# 12V_PowerSupply_V02.net
KiCad netlist of a schematic drawn in EAGLE
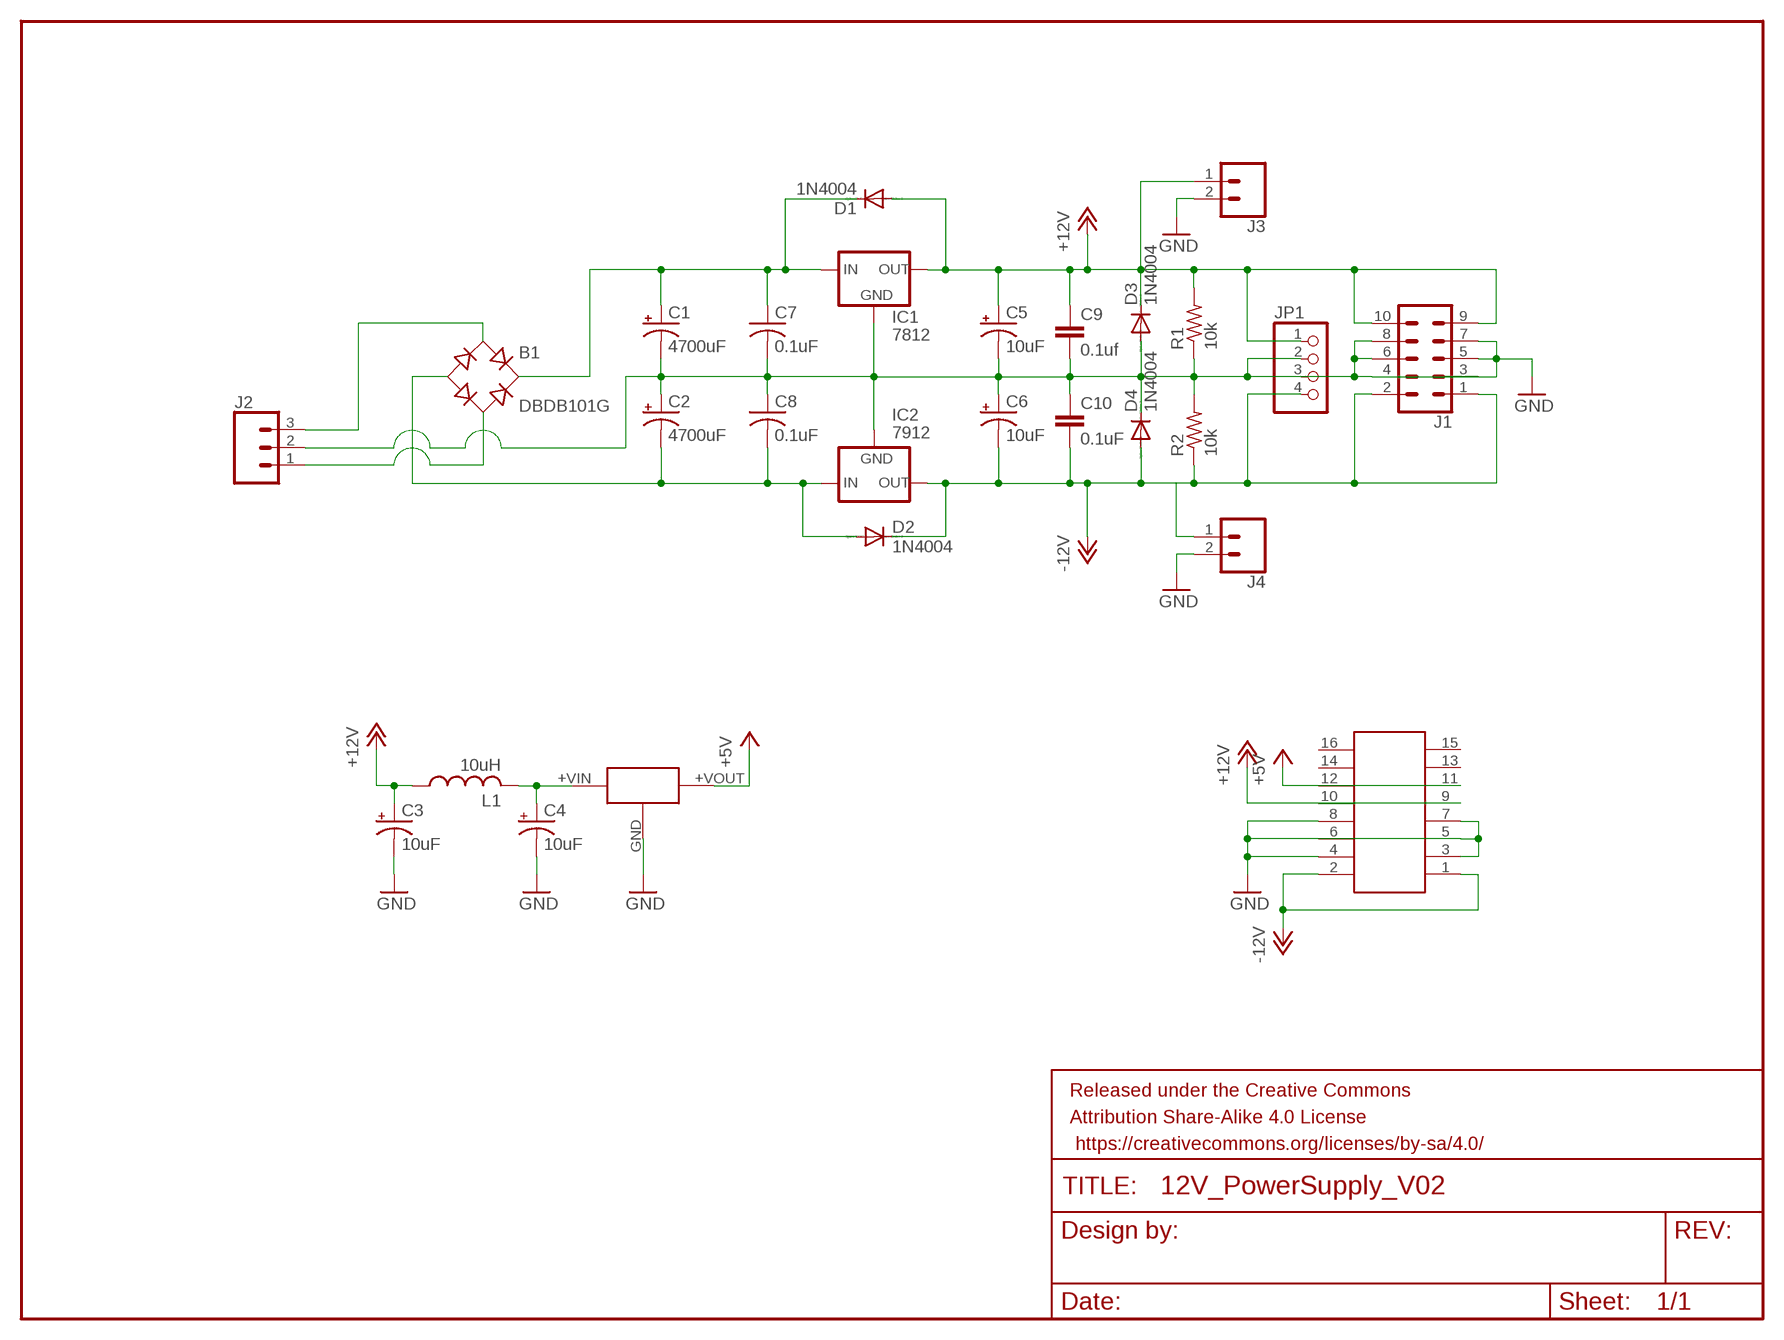
[diagram p0: schematic, sheet 1]

(export (version "E")
  (design (tool "Eeschema 10.0.6"))
  (components
    (comp (ref "B1")
      (value "DBDB101G")
      (footprint "eagle-import:DB")
      (libsource (lib "eagle-import") (part "DB?GDB101"))
    )
    (comp (ref "C1")
      (value "4700uF")
      (footprint "eagle-import:E7,5-18")
      (libsource (lib "eagle-import") (part "CPOL-USE7.5-18"))
    )
    (comp (ref "C2")
      (value "4700uF")
      (footprint "eagle-import:E7,5-18")
      (libsource (lib "eagle-import") (part "CPOL-USE7.5-18"))
    )
    (comp (ref "C3")
      (value "10uF")
      (footprint "eagle-import:E2,5-7")
      (libsource (lib "eagle-import") (part "CPOL-USE2.5-7"))
    )
    (comp (ref "C4")
      (value "10uF")
      (footprint "eagle-import:E2,5-7")
      (libsource (lib "eagle-import") (part "CPOL-USE2.5-7"))
    )
    (comp (ref "C5")
      (value "10uF")
      (footprint "eagle-import:E2,5-7")
      (libsource (lib "eagle-import") (part "CPOL-USE2.5-7"))
    )
    (comp (ref "C6")
      (value "10uF")
      (footprint "eagle-import:E2,5-7")
      (libsource (lib "eagle-import") (part "CPOL-USE2.5-7"))
    )
    (comp (ref "C7")
      (value "0.1uF")
      (footprint "eagle-import:C150-054X183")
      (libsource (lib "eagle-import") (part "C-US150-054X183"))
    )
    (comp (ref "C8")
      (value "0.1uF")
      (footprint "eagle-import:C150-054X183")
      (libsource (lib "eagle-import") (part "C-US150-054X183"))
    )
    (comp (ref "C9")
      (value "0.1uf")
      (footprint "eagle-import:C050-025X075")
      (libsource (lib "eagle-import") (part "C-EU050-025X075"))
    )
    (comp (ref "C10")
      (value "0.1uF")
      (footprint "eagle-import:C050-025X075")
      (libsource (lib "eagle-import") (part "C-EU050-025X075"))
    )
    (comp (ref "D1")
      (value "1N4004")
      (footprint "eagle-import:DO41-10")
      (libsource (lib "eagle-import") (part "1N4004"))
    )
    (comp (ref "D2")
      (value "1N4004")
      (footprint "eagle-import:DO41-10")
      (libsource (lib "eagle-import") (part "1N4004"))
    )
    (comp (ref "D3")
      (value "1N4004")
      (footprint "eagle-import:DO41-10")
      (libsource (lib "eagle-import") (part "1N4004"))
    )
    (comp (ref "D4")
      (value "1N4004")
      (footprint "eagle-import:DO41-10")
      (libsource (lib "eagle-import") (part "1N4004"))
    )
    (comp (ref "FRAME1")
      (value "FRAME-LETTER")
      (footprint "eagle-import:CREATIVE_COMMONS")
      (libsource (lib "eagle-import") (part "FRAME-LETTER"))
    )
    (comp (ref "IC1")
      (value "7812")
      (footprint "eagle-import:78XXS")
      (libsource (lib "eagle-import") (part "78XXS"))
    )
    (comp (ref "IC2")
      (value "7912")
      (footprint "eagle-import:79XXS")
      (libsource (lib "eagle-import") (part "79XXS"))
    )
    (comp (ref "J1")
      (value "CONN_05X2SHD")
      (footprint "eagle-import:2X5-SHROUDED")
      (libsource (lib "eagle-import") (part "CONN_05X2SHD"))
    )
    (comp (ref "J2")
      (value "CONN_03-SCREW-5MM")
      (footprint "eagle-import:SCREWTERMINAL-5MM-3")
      (libsource (lib "eagle-import") (part "CONN_03-SCREW-5MM"))
    )
    (comp (ref "J3")
      (value "CONN_023.5MM-NO_SILK")
      (footprint "eagle-import:SCREWTERMINAL-3.5MM-2-NS")
      (libsource (lib "eagle-import") (part "CONN_023.5MM-NO_SILK"))
    )
    (comp (ref "J4")
      (value "CONN_023.5MM-NO_SILK")
      (footprint "eagle-import:SCREWTERMINAL-3.5MM-2-NS")
      (libsource (lib "eagle-import") (part "CONN_023.5MM-NO_SILK"))
    )
    (comp (ref "JP1")
      (value "PINHD-1X4")
      (footprint "eagle-import:1X04")
      (libsource (lib "eagle-import") (part "PINHD-1X4"))
    )
    (comp (ref "L1")
      (value "10uH")
      (footprint "eagle-import:6000-XXXX-RC")
      (libsource (lib "eagle-import") (part "L-US6000-XXX-RC"))
    )
    (comp (ref "R1")
      (value "10k")
      (footprint "eagle-import:0204_7")
      (libsource (lib "eagle-import") (part "R-US_0204/7"))
    )
    (comp (ref "R2")
      (value "10k")
      (footprint "eagle-import:0204_7")
      (libsource (lib "eagle-import") (part "R-US_0204/7"))
    )
    (comp (ref "U$1")
      (value "8X2_HEADER_SHROUDED")
      (footprint "eagle-import:8X2_HEADER_SHROUDED")
      (libsource (lib "eagle-import") (part "8X2_HEADER_SHROUDED"))
    )
    (comp (ref "U$2")
      (value "R_78E_5V")
      (footprint "eagle-import:R_78E")
      (libsource (lib "eagle-import") (part "R_78E_5V"))
    )
  )
  (nets
    (net (code "1") (name "+5V") (class "Default")
      (node (ref "U$1") (pin "11") (pinfunction "11_11") (pintype "bidirectional"))
      (node (ref "U$1") (pin "12") (pinfunction "12_12") (pintype "bidirectional"))
      (node (ref "U$2") (pin "+VOUT") (pinfunction "+VOUT_+VOUT") (pintype "bidirectional"))
    )
    (net (code "2") (name "+12V") (class "Default")
      (node (ref "C3") (pin "+") (pinfunction "+_+") (pintype "passive"))
      (node (ref "C5") (pin "+") (pinfunction "+_+") (pintype "passive"))
      (node (ref "C9") (pin "1") (pinfunction "1_1") (pintype "passive"))
      (node (ref "D1") (pin "A") (pinfunction "A_A") (pintype "passive"))
      (node (ref "D3") (pin "C") (pinfunction "C_C") (pintype "passive"))
      (node (ref "IC1") (pin "OUT") (pinfunction "OUT_OUT") (pintype "passive"))
      (node (ref "J1") (pin "10") (pinfunction "10_10") (pintype "passive"))
      (node (ref "J1") (pin "9") (pinfunction "9_9") (pintype "passive"))
      (node (ref "J3") (pin "1") (pinfunction "1_1") (pintype "passive"))
      (node (ref "JP1") (pin "1") (pinfunction "1_1") (pintype "passive"))
      (node (ref "L1") (pin "1") (pinfunction "1_1") (pintype "passive"))
      (node (ref "R1") (pin "2") (pinfunction "2_2") (pintype "passive"))
      (node (ref "U$1") (pin "10") (pinfunction "10_10") (pintype "bidirectional"))
      (node (ref "U$1") (pin "9") (pinfunction "9_9") (pintype "bidirectional"))
    )
    (net (code "3") (name "-12V") (class "Default")
      (node (ref "C10") (pin "2") (pinfunction "2_2") (pintype "passive"))
      (node (ref "C6") (pin "-") (pinfunction "-_-") (pintype "passive"))
      (node (ref "D2") (pin "C") (pinfunction "C_C") (pintype "passive"))
      (node (ref "D4") (pin "A") (pinfunction "A_A") (pintype "passive"))
      (node (ref "IC2") (pin "OUT") (pinfunction "OUT_OUT") (pintype "passive"))
      (node (ref "J1") (pin "1") (pinfunction "1_1") (pintype "passive"))
      (node (ref "J1") (pin "2") (pinfunction "2_2") (pintype "passive"))
      (node (ref "J4") (pin "1") (pinfunction "1_1") (pintype "passive"))
      (node (ref "JP1") (pin "4") (pinfunction "4_4") (pintype "passive"))
      (node (ref "R2") (pin "1") (pinfunction "1_1") (pintype "passive"))
      (node (ref "U$1") (pin "1") (pinfunction "1_1") (pintype "bidirectional"))
      (node (ref "U$1") (pin "2") (pinfunction "2_2") (pintype "bidirectional"))
    )
    (net (code "4") (name "GND") (class "Default")
      (node (ref "C1") (pin "-") (pinfunction "-_-") (pintype "passive"))
      (node (ref "C10") (pin "1") (pinfunction "1_1") (pintype "passive"))
      (node (ref "C2") (pin "+") (pinfunction "+_+") (pintype "passive"))
      (node (ref "C3") (pin "-") (pinfunction "-_-") (pintype "passive"))
      (node (ref "C4") (pin "-") (pinfunction "-_-") (pintype "passive"))
      (node (ref "C5") (pin "-") (pinfunction "-_-") (pintype "passive"))
      (node (ref "C6") (pin "+") (pinfunction "+_+") (pintype "passive"))
      (node (ref "C7") (pin "2") (pinfunction "2_2") (pintype "passive"))
      (node (ref "C8") (pin "1") (pinfunction "1_1") (pintype "passive"))
      (node (ref "C9") (pin "2") (pinfunction "2_2") (pintype "passive"))
      (node (ref "D3") (pin "A") (pinfunction "A_A") (pintype "passive"))
      (node (ref "D4") (pin "C") (pinfunction "C_C") (pintype "passive"))
      (node (ref "IC1") (pin "GND") (pinfunction "GND_GND") (pintype "input"))
      (node (ref "IC2") (pin "GND") (pinfunction "GND_GND") (pintype "input"))
      (node (ref "J1") (pin "3") (pinfunction "3_3") (pintype "passive"))
      (node (ref "J1") (pin "4") (pinfunction "4_4") (pintype "passive"))
      (node (ref "J1") (pin "5") (pinfunction "5_5") (pintype "passive"))
      (node (ref "J1") (pin "6") (pinfunction "6_6") (pintype "passive"))
      (node (ref "J1") (pin "7") (pinfunction "7_7") (pintype "passive"))
      (node (ref "J1") (pin "8") (pinfunction "8_8") (pintype "passive"))
      (node (ref "J2") (pin "2") (pinfunction "2_2") (pintype "passive"))
      (node (ref "J3") (pin "2") (pinfunction "2_2") (pintype "passive"))
      (node (ref "J4") (pin "2") (pinfunction "2_2") (pintype "passive"))
      (node (ref "JP1") (pin "2") (pinfunction "2_2") (pintype "passive"))
      (node (ref "JP1") (pin "3") (pinfunction "3_3") (pintype "passive"))
      (node (ref "R1") (pin "1") (pinfunction "1_1") (pintype "passive"))
      (node (ref "R2") (pin "2") (pinfunction "2_2") (pintype "passive"))
      (node (ref "U$1") (pin "3") (pinfunction "3_3") (pintype "bidirectional"))
      (node (ref "U$1") (pin "4") (pinfunction "4_4") (pintype "bidirectional"))
      (node (ref "U$1") (pin "5") (pinfunction "5_5") (pintype "bidirectional"))
      (node (ref "U$1") (pin "6") (pinfunction "6_6") (pintype "bidirectional"))
      (node (ref "U$1") (pin "7") (pinfunction "7_7") (pintype "bidirectional"))
      (node (ref "U$1") (pin "8") (pinfunction "8_8") (pintype "bidirectional"))
      (node (ref "U$2") (pin "GND") (pinfunction "GND_GND") (pintype "bidirectional"))
    )
    (net (code "5") (name "Net-(B1-Pad+)") (class "Default")
      (node (ref "B1") (pin "+") (pinfunction "+_+") (pintype "passive"))
      (node (ref "C1") (pin "+") (pinfunction "+_+") (pintype "passive"))
      (node (ref "C7") (pin "1") (pinfunction "1_1") (pintype "passive"))
      (node (ref "D1") (pin "C") (pinfunction "C_C") (pintype "passive"))
      (node (ref "IC1") (pin "IN") (pinfunction "IN_IN") (pintype "input"))
    )
    (net (code "6") (name "Net-(B1-Pad-)") (class "Default")
      (node (ref "B1") (pin "-") (pinfunction "-_-") (pintype "passive"))
      (node (ref "C2") (pin "-") (pinfunction "-_-") (pintype "passive"))
      (node (ref "C8") (pin "2") (pinfunction "2_2") (pintype "passive"))
      (node (ref "D2") (pin "A") (pinfunction "A_A") (pintype "passive"))
      (node (ref "IC2") (pin "IN") (pinfunction "IN_IN") (pintype "input"))
    )
    (net (code "7") (name "Net-(B1-PadAC1)") (class "Default")
      (node (ref "B1") (pin "AC1") (pinfunction "AC1_AC1") (pintype "passive"))
      (node (ref "J2") (pin "3") (pinfunction "3_3") (pintype "passive"))
    )
    (net (code "8") (name "Net-(B1-PadAC2)") (class "Default")
      (node (ref "B1") (pin "AC2") (pinfunction "AC2_AC2") (pintype "passive"))
      (node (ref "J2") (pin "1") (pinfunction "1_1") (pintype "passive"))
    )
    (net (code "9") (name "Net-(C4-Pad+)") (class "Default")
      (node (ref "C4") (pin "+") (pinfunction "+_+") (pintype "passive"))
      (node (ref "L1") (pin "2") (pinfunction "2_2") (pintype "passive"))
      (node (ref "U$2") (pin "+VIN") (pinfunction "+VIN_+VIN") (pintype "bidirectional"))
    )
    (net (code "10") (name "unconnected-(U$1-Pad13)") (class "Default")
      (node (ref "U$1") (pin "13") (pinfunction "13_13") (pintype "bidirectional"))
    )
    (net (code "11") (name "unconnected-(U$1-Pad14)") (class "Default")
      (node (ref "U$1") (pin "14") (pinfunction "14_14") (pintype "bidirectional"))
    )
    (net (code "12") (name "unconnected-(U$1-Pad15)") (class "Default")
      (node (ref "U$1") (pin "15") (pinfunction "15_15") (pintype "bidirectional"))
    )
    (net (code "13") (name "unconnected-(U$1-Pad16)") (class "Default")
      (node (ref "U$1") (pin "16") (pinfunction "16_16") (pintype "bidirectional"))
    )
  )
)
